# OpenMEA_power.net
KiCad netlist of a schematic drawn in Altium Designer
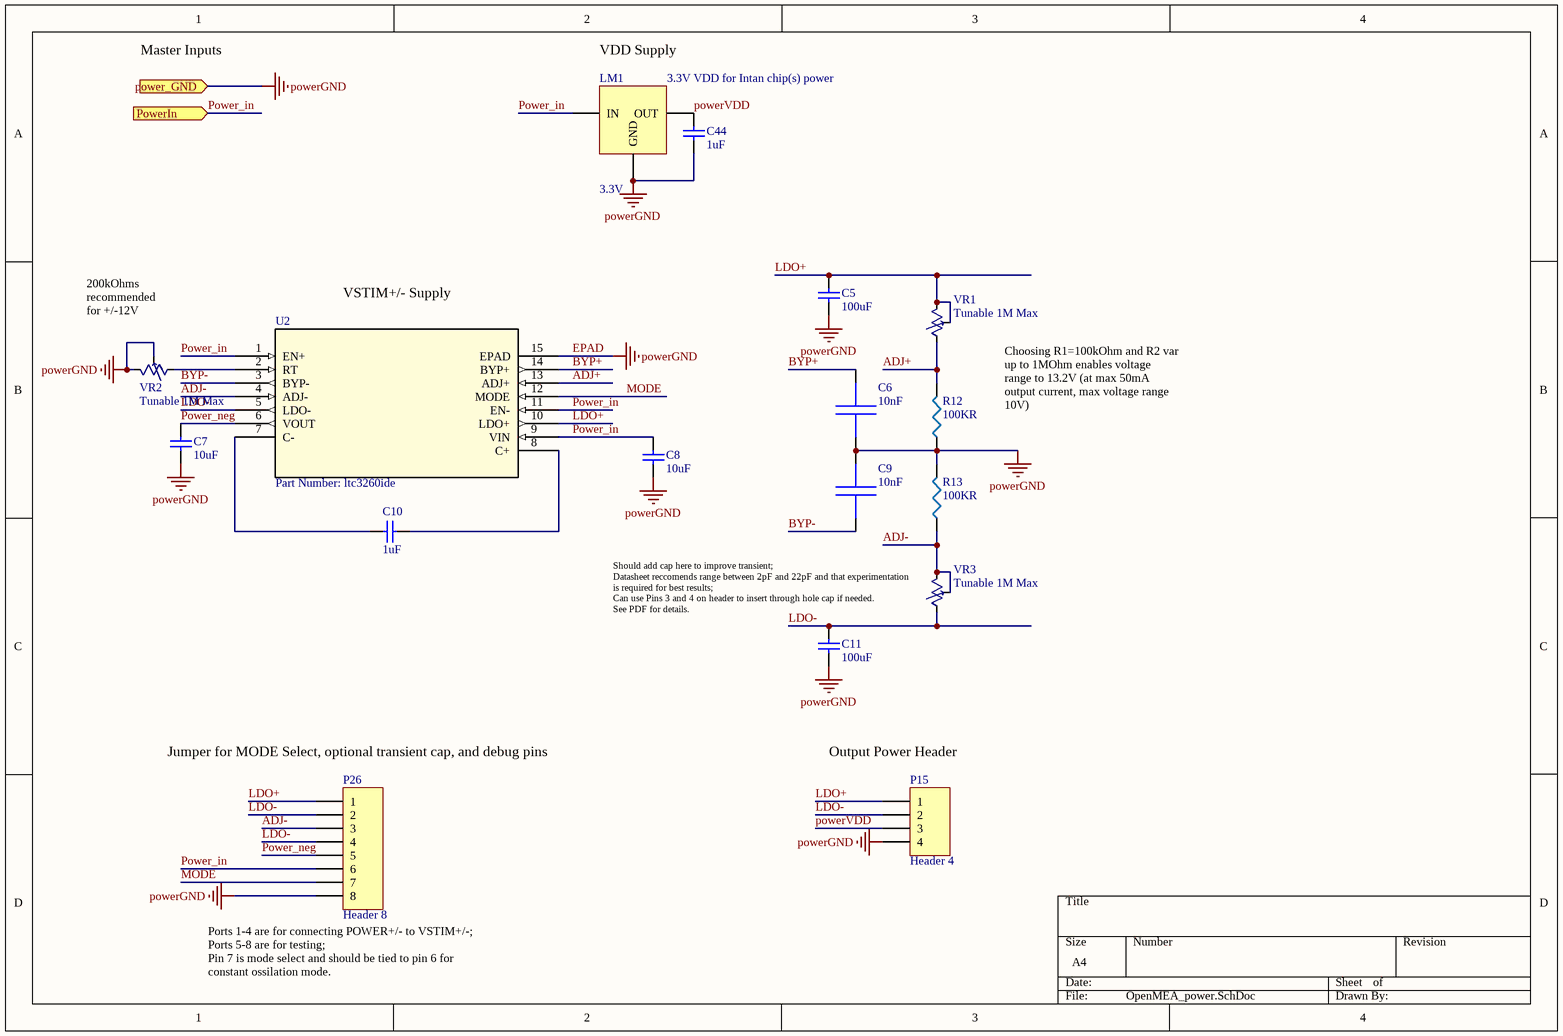
[diagram p0: OpenMEA_power.SchDoc]

(export (version "E")
  (design (tool "Eeschema 10.0.6"))
  (components
    (comp (ref "C5")
      (value "100uF")
      (footprint "panasonic_capacitors:CAP_EEFK_D")
      (description "CAP ALUM 100UF 20% 35V SMD")
      (fields
        (field (name "MANUFACTURER") "Panasonic Electronic Components")
        (field (name "MANUFACTURER PART NUMBER") "EEE-FT1V101AP")
      )
      (libsource (lib "standard_components") (part "C2012X5R1E106K085AC"))
    )
    (comp (ref "C6")
      (value "10nF")
      (footprint "rcl_0402i_1005m_nominal")
      (description "Capacitor Non-polarized American Symbol")
      (fields
        (field (name "MANUFACTURER") "Murata Electronics North America")
        (field (name "MANUFACTURER PART NUMBER") "GRM155R71E103KA01D")
      )
      (libsource (lib "rcl_passives") (part "capacitor_npol_ame"))
    )
    (comp (ref "C7")
      (value "10uF")
      (footprint "Thesis_Testboard_V1I1:C0805")
      (description "CAP 10UF")
      (fields
        (field (name "MANUFACTURER") "Samsung Electro-Mechanics")
        (field (name "MANUFACTURER PART NUMBER") "CL21A106KAYNNNE")
      )
      (libsource (lib "standard_components") (part "C2012X5R1E106K085AC"))
    )
    (comp (ref "C8")
      (value "10uF")
      (footprint "Thesis_Testboard_V1I1:C0805")
      (description "CAP 10UF")
      (fields
        (field (name "MANUFACTURER") "Samsung Electro-Mechanics")
        (field (name "MANUFACTURER PART NUMBER") "CL21A106KAYNNNE")
      )
      (libsource (lib "standard_components") (part "C2012X5R1E106K085AC"))
    )
    (comp (ref "C9")
      (value "10nF")
      (footprint "rcl_0402i_1005m_nominal")
      (description "Capacitor Non-polarized American Symbol")
      (fields
        (field (name "MANUFACTURER") "Murata Electronics North America")
        (field (name "MANUFACTURER PART NUMBER") "GRM155R71E103KA01D")
      )
      (libsource (lib "rcl_passives") (part "capacitor_npol_ame"))
    )
    (comp (ref "C10")
      (value "1uF")
      (footprint "standard_components:C0805")
      (description "CAP 1UF")
      (fields
        (field (name "MANUFACTURER") "TDK")
        (field (name "MANUFACTURER PART NUMBER") "C2012X5R1E105K125AA")
      )
      (libsource (lib "standard_components") (part "C2012X5R1E105K125AA"))
    )
    (comp (ref "C11")
      (value "100uF")
      (footprint "panasonic_capacitors:CAP_EEFK_D")
      (description "CAP ALUM 100UF 20% 35V SMD")
      (fields
        (field (name "MANUFACTURER") "Panasonic Electronic Components")
        (field (name "MANUFACTURER PART NUMBER") "EEE-FT1V101AP")
      )
      (libsource (lib "standard_components") (part "C2012X5R1E106K085AC"))
    )
    (comp (ref "C44")
      (value "1uF")
      (footprint "standard_components:C0805")
      (description "CAP 1UF")
      (fields
        (field (name "MANUFACTURER") "TDK")
        (field (name "MANUFACTURER PART NUMBER") "C2012X5R1E105K125AA")
      )
      (libsource (lib "standard_components") (part "C2012X5R1E105K125AA"))
    )
    (comp (ref "LM1")
      (value "3.3V")
      (footprint "LM1085")
      (description "LM1085ISX-3.3/NOPB")
      (fields (field (name "MANUFACTURER") "TI National Semiconductor"))
      (libsource (lib "power") (part "LM1085"))
    )
    (comp (ref "P15")
      (value "Header 4")
      (footprint "on_shore_rising_clamp:OSTVN04A150")
      (description "Header, 4-Pin")
      (fields
        (field (name "MANUFACTURER") "On Shore Technology Inc.")
        (field (name "MANUFACTURER PART NUMBER") "OSTVN04A150")
        (field (name "PUBLISHER") "Altium Limited")
      )
      (libsource (lib "standard_components") (part "Header 4"))
    )
    (comp (ref "P26")
      (value "Header 8")
      (footprint "te_connectivity_headers:TE_5-535541-6")
      (description "Header, 8-Pin")
      (fields
        (field (name "MANUFACTURER") "TE Connectivity AMP Connectors")
        (field (name "MANUFACTURER PART NUMBER") "5-535541-6")
      )
      (libsource (lib "standard_components") (part "Header 8"))
    )
    (comp (ref "R12")
      (value "100KR")
      (footprint "standard_components:R0805")
      (description "CRCW0805100KFKEA")
      (fields (field (name "MANUFACTURER") "Vishay Dale") (field (name "TOLERANCE") "1%"))
      (libsource (lib "standard_components") (part "RES100"))
    )
    (comp (ref "R13")
      (value "100KR")
      (footprint "standard_components:R0805")
      (description "CRCW0805100KFKEA")
      (fields (field (name "MANUFACTURER") "Vishay Dale") (field (name "TOLERANCE") "1%"))
      (libsource (lib "standard_components") (part "RES100"))
    )
    (comp (ref "U2")
      (value "Part Number: ltc3260ide")
      (footprint "analog_devices_power:DFN-14_DE")
      (description "IC REG CHARGE PUMP INV 14DFN")
      (fields
        (field (name "MANUFACTURER_PART_NUMBER") "ltc3260ide")
        (field (name "MANUFACTURER") "Linear Technology/Analog Devices")
        (field (name "COPYRIGHT") "Copyright (C) 2018 Accelerated Designs. All rights reserved")
      )
      (libsource (lib "analog_devices_power") (part "LTC3260IDE"))
    )
    (comp (ref "VR1")
      (value "Tunable 1M Max")
      (footprint "Thesis_Testboard_V1I1:res_var_5turn")
      (description "TRIMMER 1M OHM 0.25W J LEAD TOP")
      (fields
        (field (name "MANUFACTURER") "Nidec Copal")
        (field (name "MANUFACTURER PART NUMBER") "SM-42TW105")
      )
      (libsource (lib "standard_components") (part "RES_VAR_5TURN"))
    )
    (comp (ref "VR2")
      (value "Tunable 1M Max")
      (footprint "Thesis_Testboard_V1I1:res_var_5turn")
      (description "TRIMMER 1M OHM 0.25W J LEAD TOP")
      (fields
        (field (name "MANUFACTURER") "Nidec Copal")
        (field (name "MANUFACTURER PART NUMBER") "SM-42TW105")
      )
      (libsource (lib "standard_components") (part "RES_VAR_5TURN"))
    )
    (comp (ref "VR3")
      (value "Tunable 1M Max")
      (footprint "Thesis_Testboard_V1I1:res_var_5turn")
      (description "TRIMMER 1M OHM 0.25W J LEAD TOP")
      (fields
        (field (name "MANUFACTURER") "Nidec Copal")
        (field (name "MANUFACTURER PART NUMBER") "SM-42TW105")
      )
      (libsource (lib "standard_components") (part "RES_VAR_5TURN"))
    )
  )
  (nets
    (net (code "1") (name "/ADJ+") (class "Default")
      (node (ref "R12") (pin "2") (pinfunction "2_2") (pintype "passive"))
      (node (ref "U2") (pin "13") (pinfunction "ADJ+_13") (pintype "input"))
      (node (ref "VR1") (pin "3") (pintype "passive"))
    )
    (net (code "2") (name "/ADJ-") (class "Default")
      (node (ref "P26") (pin "3") (pinfunction "3_3") (pintype "passive"))
      (node (ref "R13") (pin "1") (pinfunction "1_1") (pintype "passive"))
      (node (ref "U2") (pin "4") (pinfunction "ADJ-_4") (pintype "input"))
      (node (ref "VR3") (pin "1") (pintype "passive"))
      (node (ref "VR3") (pin "2") (pintype "passive"))
    )
    (net (code "3") (name "/BYP+") (class "Default")
      (node (ref "C6") (pin "2") (pinfunction "2_2") (pintype "passive"))
      (node (ref "U2") (pin "14") (pinfunction "BYP+_14") (pintype "output"))
    )
    (net (code "4") (name "/BYP-") (class "Default")
      (node (ref "C9") (pin "2") (pinfunction "2_2") (pintype "passive"))
      (node (ref "U2") (pin "3") (pinfunction "BYP-_3") (pintype "output"))
    )
    (net (code "5") (name "/LDO+") (class "Default")
      (node (ref "C5") (pin "2") (pinfunction "2_2") (pintype "passive"))
      (node (ref "P15") (pin "1") (pinfunction "1_1") (pintype "passive"))
      (node (ref "P26") (pin "1") (pinfunction "1_1") (pintype "passive"))
      (node (ref "U2") (pin "10") (pinfunction "LDO+_10") (pintype "output"))
      (node (ref "VR1") (pin "1") (pintype "passive"))
      (node (ref "VR1") (pin "2") (pintype "passive"))
    )
    (net (code "6") (name "/LDO-") (class "Default")
      (node (ref "C11") (pin "2") (pinfunction "2_2") (pintype "passive"))
      (node (ref "P15") (pin "2") (pinfunction "2_2") (pintype "passive"))
      (node (ref "P26") (pin "2") (pinfunction "2_2") (pintype "passive"))
      (node (ref "P26") (pin "4") (pinfunction "4_4") (pintype "passive"))
      (node (ref "U2") (pin "5") (pinfunction "LDO-_5") (pintype "output"))
      (node (ref "VR3") (pin "3") (pintype "passive"))
    )
    (net (code "7") (name "/MODE") (class "Default")
      (node (ref "P26") (pin "7") (pinfunction "7_7") (pintype "passive"))
      (node (ref "U2") (pin "12") (pinfunction "MODE_12") (pintype "input"))
    )
    (net (code "8") (name "/Power_in") (class "Default")
      (node (ref "C8") (pin "2") (pinfunction "2_2") (pintype "passive"))
      (node (ref "LM1") (pin "3") (pinfunction "IN_3") (pintype "passive"))
      (node (ref "P26") (pin "6") (pinfunction "6_6") (pintype "passive"))
      (node (ref "U2") (pin "1") (pinfunction "EN+_1") (pintype "input"))
      (node (ref "U2") (pin "11") (pinfunction "EN-_11") (pintype "input"))
      (node (ref "U2") (pin "9") (pinfunction "VIN_9") (pintype "input"))
    )
    (net (code "9") (name "/Power_neg") (class "Default")
      (node (ref "C7") (pin "2") (pinfunction "2_2") (pintype "passive"))
      (node (ref "P26") (pin "5") (pinfunction "5_5") (pintype "passive"))
      (node (ref "U2") (pin "6") (pinfunction "VOUT_6") (pintype "output"))
    )
    (net (code "10") (name "/powerVDD") (class "Default")
      (node (ref "C44") (pin "2") (pinfunction "2_2") (pintype "passive"))
      (node (ref "LM1") (pin "2") (pinfunction "OUT_2") (pintype "passive"))
      (node (ref "P15") (pin "3") (pinfunction "3_3") (pintype "passive"))
    )
    (net (code "11") (name "Net-(U2-C+)") (class "Default")
      (node (ref "C10") (pin "1") (pinfunction "1_1") (pintype "passive"))
      (node (ref "U2") (pin "8") (pinfunction "C+_8") (pintype "passive"))
    )
    (net (code "12") (name "Net-(U2-C-)") (class "Default")
      (node (ref "C10") (pin "2") (pinfunction "2_2") (pintype "passive"))
      (node (ref "U2") (pin "7") (pinfunction "C-_7") (pintype "passive"))
    )
    (net (code "13") (name "Net-(U2-RT)") (class "Default")
      (node (ref "U2") (pin "2") (pinfunction "RT_2") (pintype "input"))
      (node (ref "VR2") (pin "3") (pintype "passive"))
    )
    (net (code "14") (name "powerGND") (class "Default")
      (node (ref "C11") (pin "1") (pinfunction "1_1") (pintype "passive"))
      (node (ref "C44") (pin "1") (pinfunction "1_1") (pintype "passive"))
      (node (ref "C5") (pin "1") (pinfunction "1_1") (pintype "passive"))
      (node (ref "C6") (pin "1") (pinfunction "1_1") (pintype "passive"))
      (node (ref "C7") (pin "1") (pinfunction "1_1") (pintype "passive"))
      (node (ref "C8") (pin "1") (pinfunction "1_1") (pintype "passive"))
      (node (ref "C9") (pin "1") (pinfunction "1_1") (pintype "passive"))
      (node (ref "LM1") (pin "1") (pinfunction "GND_1") (pintype "passive"))
      (node (ref "P15") (pin "4") (pinfunction "4_4") (pintype "passive"))
      (node (ref "P26") (pin "8") (pinfunction "8_8") (pintype "passive"))
      (node (ref "R12") (pin "1") (pinfunction "1_1") (pintype "passive"))
      (node (ref "R13") (pin "2") (pinfunction "2_2") (pintype "passive"))
      (node (ref "U2") (pin "15") (pinfunction "EPAD_15") (pintype "passive"))
      (node (ref "VR2") (pin "1") (pintype "passive"))
      (node (ref "VR2") (pin "2") (pintype "passive"))
    )
  )
)
